# Mult-tl084.net
KiCad netlist of a schematic drawn in EAGLE
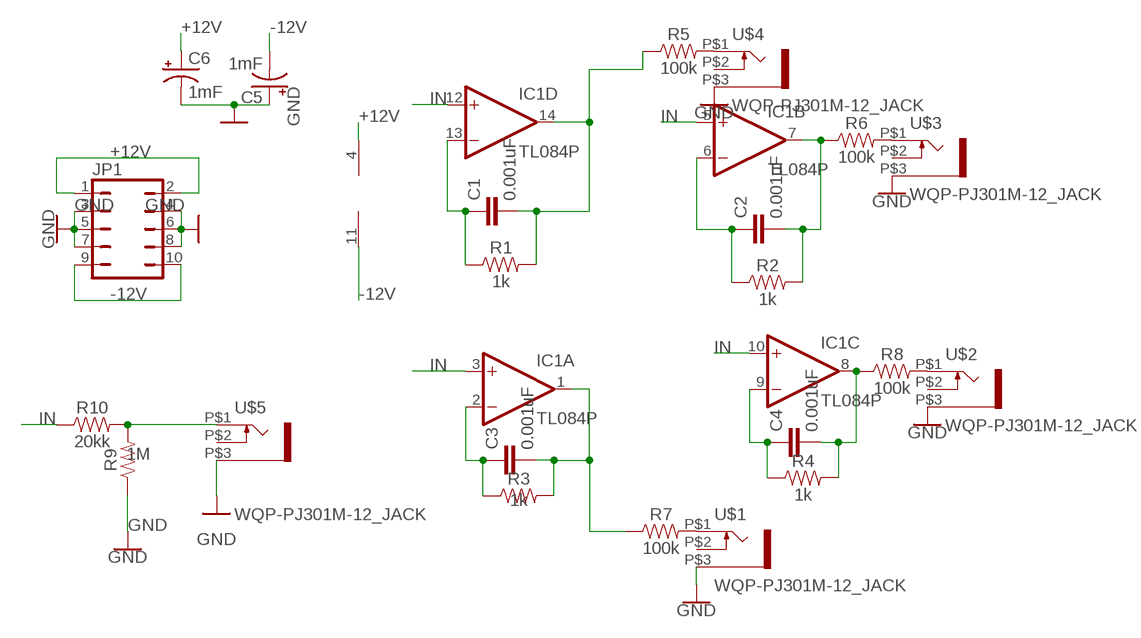
[diagram p0: schematic, sheet 1]

(export (version "E")
  (design (tool "Eeschema 10.0.6"))
  (components
    (comp (ref "C1")
      (value "0.001uF")
      (footprint "eagle-import:CAP-PTH-SMALL-KIT")
      (libsource (lib "eagle-import") (part "0.1UF-KIT-EZ-50V-20%"))
    )
    (comp (ref "C2")
      (value "0.001uF")
      (footprint "eagle-import:CAP-PTH-SMALL-KIT")
      (libsource (lib "eagle-import") (part "0.1UF-KIT-EZ-50V-20%"))
    )
    (comp (ref "C3")
      (value "0.001uF")
      (footprint "eagle-import:CAP-PTH-SMALL-KIT")
      (libsource (lib "eagle-import") (part "0.1UF-KIT-EZ-50V-20%"))
    )
    (comp (ref "C4")
      (value "0.001uF")
      (footprint "eagle-import:CAP-PTH-SMALL-KIT")
      (libsource (lib "eagle-import") (part "0.1UF-KIT-EZ-50V-20%"))
    )
    (comp (ref "C5")
      (value "1mF")
      (footprint "eagle-import:CPOL-RADIAL-5MM-10MM")
      (libsource (lib "eagle-import") (part "1000UF-RADIAL-5MM-25V-20%"))
    )
    (comp (ref "C6")
      (value "1mF")
      (footprint "eagle-import:CPOL-RADIAL-5MM-10MM")
      (libsource (lib "eagle-import") (part "1000UF-RADIAL-5MM-25V-20%"))
    )
    (comp (ref "IC1")
      (value "TL084P")
      (footprint "eagle-import:DIL14")
      (libsource (lib "eagle-import") (part "TL084P"))
    )
    (comp (ref "JP1")
      (value "JP5Q")
      (footprint "eagle-import:JP5Q")
      (libsource (lib "eagle-import") (part "JP5Q"))
    )
    (comp (ref "R1")
      (value "1k")
      (footprint "eagle-import:AXIAL-0.3")
      (libsource (lib "eagle-import") (part "1KOHM-HORIZ-1/4W-5%"))
    )
    (comp (ref "R2")
      (value "1k")
      (footprint "eagle-import:AXIAL-0.3")
      (libsource (lib "eagle-import") (part "1KOHM-HORIZ-1/4W-5%"))
    )
    (comp (ref "R3")
      (value "1k")
      (footprint "eagle-import:AXIAL-0.3")
      (libsource (lib "eagle-import") (part "1KOHM-HORIZ-1/4W-5%"))
    )
    (comp (ref "R4")
      (value "1k")
      (footprint "eagle-import:AXIAL-0.3")
      (libsource (lib "eagle-import") (part "1KOHM-HORIZ-1/4W-5%"))
    )
    (comp (ref "R5")
      (value "100k")
      (footprint "eagle-import:AXIAL-0.3")
      (libsource (lib "eagle-import") (part "1KOHM-HORIZ-1/4W-5%"))
    )
    (comp (ref "R6")
      (value "100k")
      (footprint "eagle-import:AXIAL-0.3")
      (libsource (lib "eagle-import") (part "1KOHM-HORIZ-1/4W-5%"))
    )
    (comp (ref "R7")
      (value "100k")
      (footprint "eagle-import:AXIAL-0.3")
      (libsource (lib "eagle-import") (part "1KOHM-HORIZ-1/4W-5%"))
    )
    (comp (ref "R8")
      (value "100k")
      (footprint "eagle-import:AXIAL-0.3")
      (libsource (lib "eagle-import") (part "1KOHM-HORIZ-1/4W-5%"))
    )
    (comp (ref "R9")
      (value "1M")
      (footprint "eagle-import:AXIAL-0.3")
      (libsource (lib "eagle-import") (part "1KOHM-HORIZ-1/4W-5%"))
    )
    (comp (ref "R10")
      (value "20kk")
      (footprint "eagle-import:AXIAL-0.3")
      (libsource (lib "eagle-import") (part "1KOHM-HORIZ-1/4W-5%"))
    )
    (comp (ref "U$1")
      (value "WQP-PJ301M-12_JACK")
      (footprint "eagle-import:WQP-PJ301M-12_JACK")
      (libsource (lib "eagle-import") (part "WQP-PJ301M-12_JACK"))
    )
    (comp (ref "U$2")
      (value "WQP-PJ301M-12_JACK")
      (footprint "eagle-import:WQP-PJ301M-12_JACK")
      (libsource (lib "eagle-import") (part "WQP-PJ301M-12_JACK"))
    )
    (comp (ref "U$3")
      (value "WQP-PJ301M-12_JACK")
      (footprint "eagle-import:WQP-PJ301M-12_JACK")
      (libsource (lib "eagle-import") (part "WQP-PJ301M-12_JACK"))
    )
    (comp (ref "U$4")
      (value "WQP-PJ301M-12_JACK")
      (footprint "eagle-import:WQP-PJ301M-12_JACK")
      (libsource (lib "eagle-import") (part "WQP-PJ301M-12_JACK"))
    )
    (comp (ref "U$5")
      (value "WQP-PJ301M-12_JACK")
      (footprint "eagle-import:WQP-PJ301M-12_JACK")
      (libsource (lib "eagle-import") (part "WQP-PJ301M-12_JACK"))
    )
  )
  (nets
    (net (code "1") (name "/+12V") (class "Default")
      (node (ref "C6") (pin "+") (pinfunction "+_+") (pintype "passive"))
      (node (ref "IC1") (pin "4") (pinfunction "V+_4") (pintype "power_in"))
      (node (ref "JP1") (pin "1") (pinfunction "1_1") (pintype "passive"))
      (node (ref "JP1") (pin "2") (pinfunction "2_2") (pintype "passive"))
    )
    (net (code "2") (name "/-12V") (class "Default")
      (node (ref "C5") (pin "-") (pinfunction "-_-") (pintype "passive"))
      (node (ref "IC1") (pin "11") (pinfunction "V-_11") (pintype "power_in"))
      (node (ref "JP1") (pin "10") (pinfunction "10_10") (pintype "passive"))
      (node (ref "JP1") (pin "9") (pinfunction "9_9") (pintype "passive"))
    )
    (net (code "3") (name "/IN") (class "Default")
      (node (ref "IC1") (pin "10") (pinfunction "+IN_10") (pintype "input"))
      (node (ref "IC1") (pin "12") (pinfunction "+IN_12") (pintype "input"))
      (node (ref "IC1") (pin "3") (pinfunction "+IN_3") (pintype "input"))
      (node (ref "IC1") (pin "5") (pinfunction "+IN_5") (pintype "input"))
      (node (ref "R10") (pin "P$1") (pinfunction "1_P$1") (pintype "passive"))
    )
    (net (code "4") (name "GND") (class "Default")
      (node (ref "C5") (pin "+") (pinfunction "+_+") (pintype "passive"))
      (node (ref "C6") (pin "-") (pinfunction "-_-") (pintype "passive"))
      (node (ref "JP1") (pin "3") (pinfunction "3_3") (pintype "passive"))
      (node (ref "JP1") (pin "4") (pinfunction "4_4") (pintype "passive"))
      (node (ref "JP1") (pin "5") (pinfunction "5_5") (pintype "passive"))
      (node (ref "JP1") (pin "6") (pinfunction "6_6") (pintype "passive"))
      (node (ref "JP1") (pin "7") (pinfunction "7_7") (pintype "passive"))
      (node (ref "JP1") (pin "8") (pinfunction "8_8") (pintype "passive"))
      (node (ref "R9") (pin "P$1") (pinfunction "1_P$1") (pintype "passive"))
      (node (ref "U$1") (pin "P$3") (pinfunction "1_P$3") (pintype "passive"))
      (node (ref "U$2") (pin "P$3") (pinfunction "1_P$3") (pintype "passive"))
      (node (ref "U$3") (pin "P$3") (pinfunction "1_P$3") (pintype "passive"))
      (node (ref "U$4") (pin "P$3") (pinfunction "1_P$3") (pintype "passive"))
      (node (ref "U$5") (pin "P$3") (pinfunction "1_P$3") (pintype "passive"))
    )
    (net (code "5") (name "Net-(IC1A--IN)") (class "Default")
      (node (ref "C3") (pin "1") (pinfunction "1_1") (pintype "passive"))
      (node (ref "IC1") (pin "2") (pinfunction "-IN_2") (pintype "input"))
      (node (ref "R3") (pin "P$1") (pinfunction "1_P$1") (pintype "passive"))
    )
    (net (code "6") (name "Net-(IC1A-OUT)") (class "Default")
      (node (ref "C3") (pin "2") (pinfunction "2_2") (pintype "passive"))
      (node (ref "IC1") (pin "1") (pinfunction "OUT_1") (pintype "output"))
      (node (ref "R3") (pin "P$2") (pinfunction "2_P$2") (pintype "passive"))
      (node (ref "R7") (pin "P$1") (pinfunction "1_P$1") (pintype "passive"))
    )
    (net (code "7") (name "Net-(IC1B--IN)") (class "Default")
      (node (ref "C2") (pin "1") (pinfunction "1_1") (pintype "passive"))
      (node (ref "IC1") (pin "6") (pinfunction "-IN_6") (pintype "input"))
      (node (ref "R2") (pin "P$1") (pinfunction "1_P$1") (pintype "passive"))
    )
    (net (code "8") (name "Net-(IC1B-OUT)") (class "Default")
      (node (ref "C2") (pin "2") (pinfunction "2_2") (pintype "passive"))
      (node (ref "IC1") (pin "7") (pinfunction "OUT_7") (pintype "output"))
      (node (ref "R2") (pin "P$2") (pinfunction "2_P$2") (pintype "passive"))
      (node (ref "R6") (pin "P$1") (pinfunction "1_P$1") (pintype "passive"))
    )
    (net (code "9") (name "Net-(IC1C--IN)") (class "Default")
      (node (ref "C4") (pin "1") (pinfunction "1_1") (pintype "passive"))
      (node (ref "IC1") (pin "9") (pinfunction "-IN_9") (pintype "input"))
      (node (ref "R4") (pin "P$1") (pinfunction "1_P$1") (pintype "passive"))
    )
    (net (code "10") (name "Net-(IC1C-OUT)") (class "Default")
      (node (ref "C4") (pin "2") (pinfunction "2_2") (pintype "passive"))
      (node (ref "IC1") (pin "8") (pinfunction "OUT_8") (pintype "output"))
      (node (ref "R4") (pin "P$2") (pinfunction "2_P$2") (pintype "passive"))
      (node (ref "R8") (pin "P$1") (pinfunction "1_P$1") (pintype "passive"))
    )
    (net (code "11") (name "Net-(IC1D--IN)") (class "Default")
      (node (ref "C1") (pin "1") (pinfunction "1_1") (pintype "passive"))
      (node (ref "IC1") (pin "13") (pinfunction "-IN_13") (pintype "input"))
      (node (ref "R1") (pin "P$1") (pinfunction "1_P$1") (pintype "passive"))
    )
    (net (code "12") (name "Net-(IC1D-OUT)") (class "Default")
      (node (ref "C1") (pin "2") (pinfunction "2_2") (pintype "passive"))
      (node (ref "IC1") (pin "14") (pinfunction "OUT_14") (pintype "output"))
      (node (ref "R1") (pin "P$2") (pinfunction "2_P$2") (pintype "passive"))
      (node (ref "R5") (pin "P$1") (pinfunction "1_P$1") (pintype "passive"))
    )
    (net (code "13") (name "Net-(R5-2)") (class "Default")
      (node (ref "R5") (pin "P$2") (pinfunction "2_P$2") (pintype "passive"))
      (node (ref "U$4") (pin "P$1") (pinfunction "2_P$1") (pintype "passive"))
    )
    (net (code "14") (name "Net-(R6-2)") (class "Default")
      (node (ref "R6") (pin "P$2") (pinfunction "2_P$2") (pintype "passive"))
      (node (ref "U$3") (pin "P$1") (pinfunction "2_P$1") (pintype "passive"))
    )
    (net (code "15") (name "Net-(R7-2)") (class "Default")
      (node (ref "R7") (pin "P$2") (pinfunction "2_P$2") (pintype "passive"))
      (node (ref "U$1") (pin "P$1") (pinfunction "2_P$1") (pintype "passive"))
    )
    (net (code "16") (name "Net-(R8-2)") (class "Default")
      (node (ref "R8") (pin "P$2") (pinfunction "2_P$2") (pintype "passive"))
      (node (ref "U$2") (pin "P$1") (pinfunction "2_P$1") (pintype "passive"))
    )
    (net (code "17") (name "Net-(R10-2)") (class "Default")
      (node (ref "R10") (pin "P$2") (pinfunction "2_P$2") (pintype "passive"))
      (node (ref "R9") (pin "P$2") (pinfunction "2_P$2") (pintype "passive"))
      (node (ref "U$5") (pin "P$1") (pinfunction "2_P$1") (pintype "passive"))
    )
    (net (code "18") (name "unconnected-(U$1-3-PadP$2)") (class "Default")
      (node (ref "U$1") (pin "P$2") (pinfunction "3_P$2") (pintype "passive"))
    )
    (net (code "19") (name "unconnected-(U$2-3-PadP$2)") (class "Default")
      (node (ref "U$2") (pin "P$2") (pinfunction "3_P$2") (pintype "passive"))
    )
    (net (code "20") (name "unconnected-(U$3-3-PadP$2)") (class "Default")
      (node (ref "U$3") (pin "P$2") (pinfunction "3_P$2") (pintype "passive"))
    )
    (net (code "21") (name "unconnected-(U$4-3-PadP$2)") (class "Default")
      (node (ref "U$4") (pin "P$2") (pinfunction "3_P$2") (pintype "passive"))
    )
    (net (code "22") (name "unconnected-(U$5-3-PadP$2)") (class "Default")
      (node (ref "U$5") (pin "P$2") (pinfunction "3_P$2") (pintype "passive"))
    )
  )
)
